# FULL_HIERARCHICAL_SCHEMATIC.net
KiCad netlist of a schematic drawn in Altium Designer
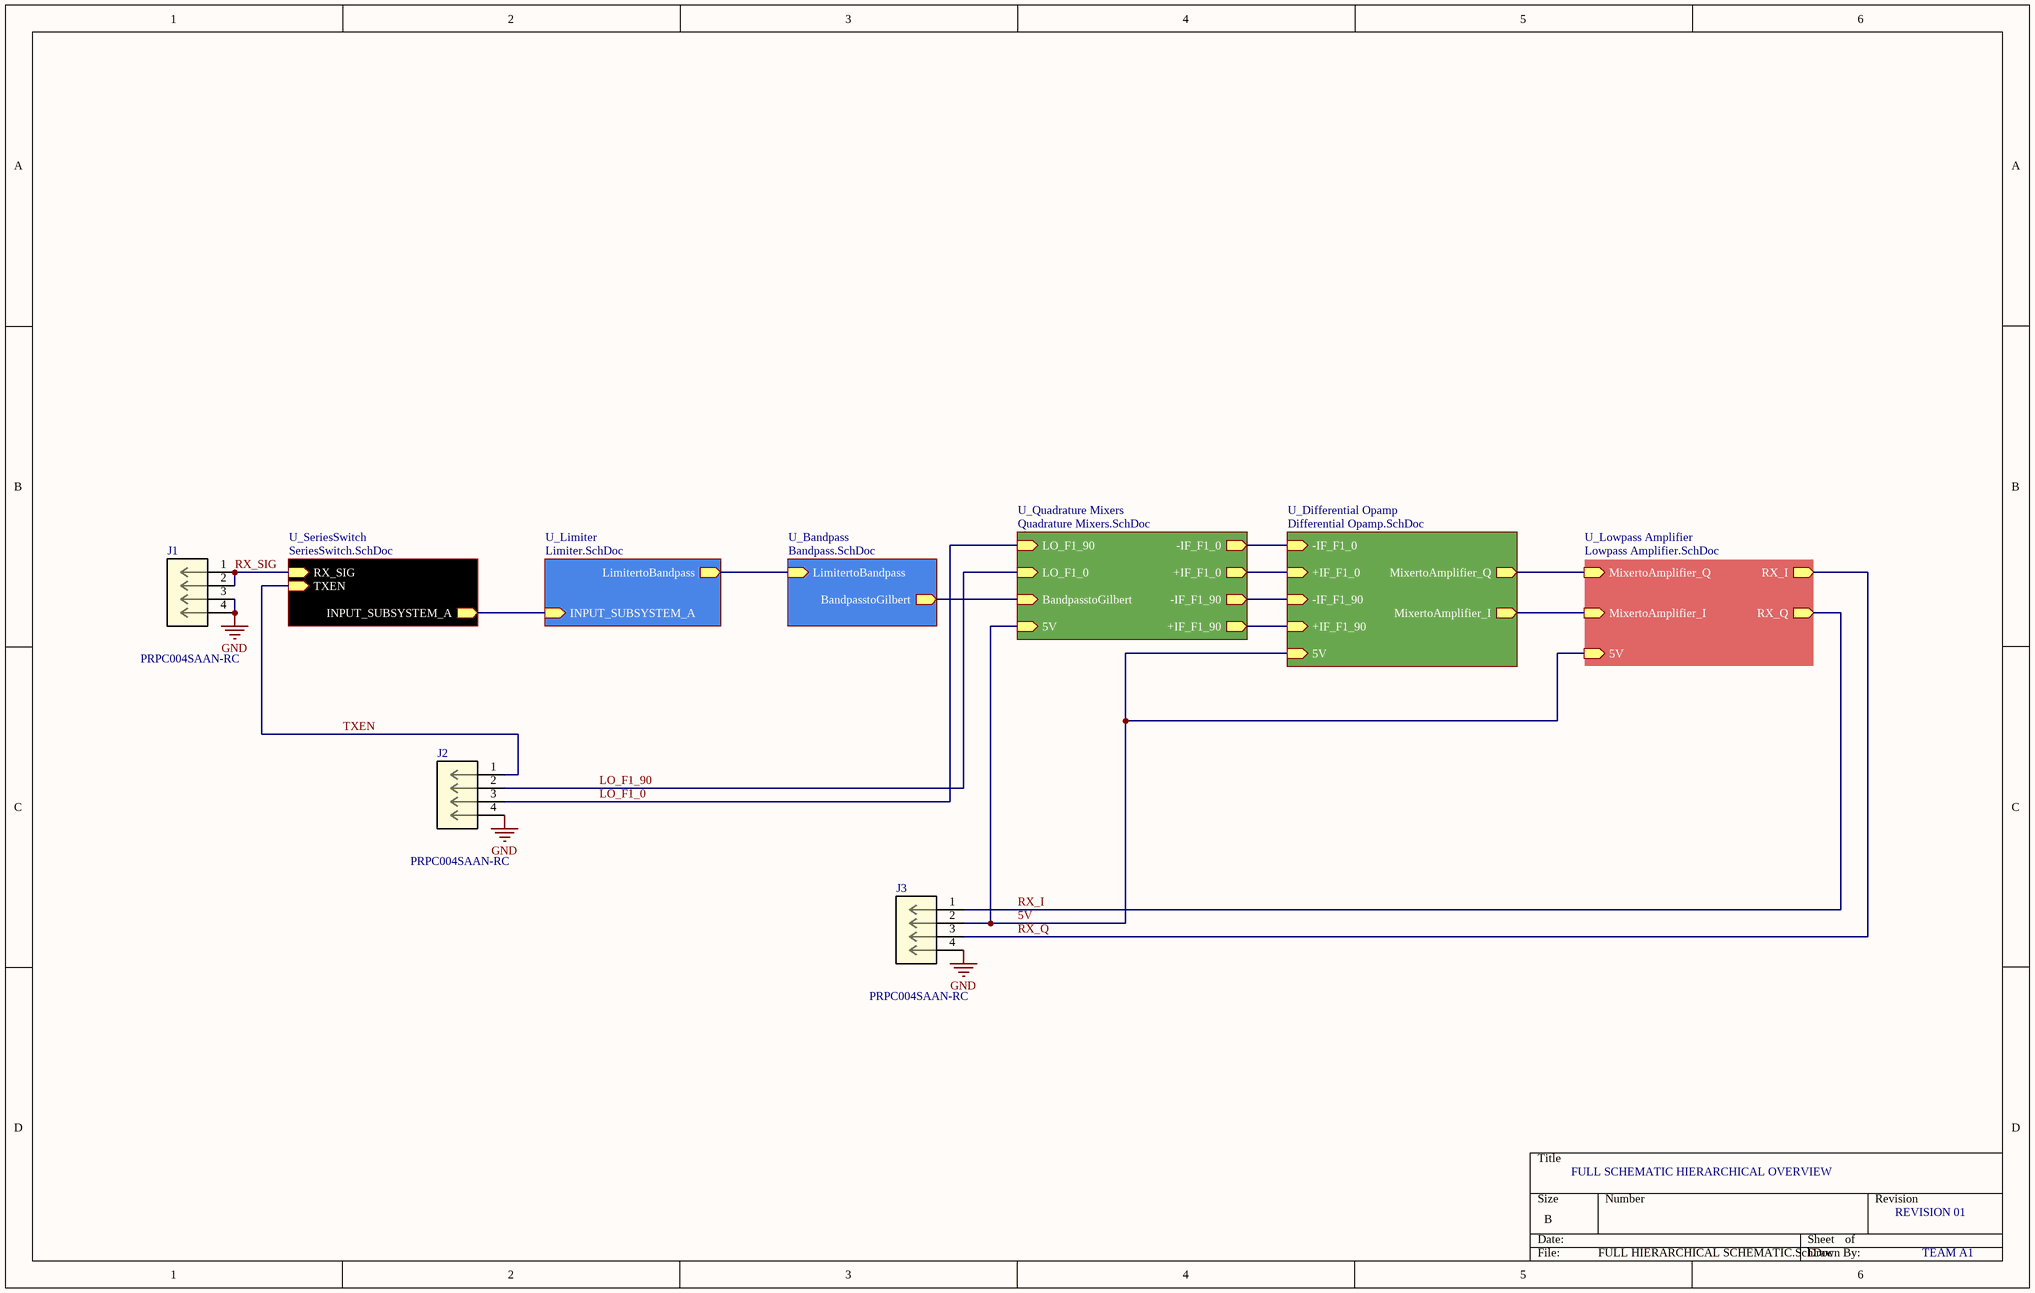
[diagram p0: FULL HIERARCHICAL SCHEMATIC.SchDoc]

(export (version "E")
  (design (tool "Eeschema 10.0.6"))
  (components
    (comp (ref "J1")
      (value "PRPC004SAAN-RC")
      (footprint "CONN4_PRPC004_SUL")
      (description "No Description Available")
      (libsource (lib "PRPC004SAAN-RC") (part "PRPC004SAAN-RC"))
    )
    (comp (ref "J2")
      (value "PRPC004SAAN-RC")
      (footprint "CONN4_PRPC004_SUL")
      (description "No Description Available")
      (libsource (lib "PRPC004SAAN-RC") (part "PRPC004SAAN-RC"))
    )
    (comp (ref "J3")
      (value "PRPC004SAAN-RC")
      (footprint "CONN4_PRPC004_SUL")
      (description "No Description Available")
      (libsource (lib "PRPC004SAAN-RC") (part "PRPC004SAAN-RC"))
    )
  )
  (nets
    (net (code "5") (name "/5V") (class "Default")
      (node (ref "J3") (pin "2") (pinfunction "2_2") (pintype "passive"))
    )
    (net (code "8") (name "/LO_F1_0") (class "Default")
      (node (ref "J2") (pin "3") (pinfunction "3_3") (pintype "passive"))
    )
    (net (code "9") (name "/LO_F1_90") (class "Default")
      (node (ref "J2") (pin "2") (pinfunction "2_2") (pintype "passive"))
    )
    (net (code "13") (name "/RX_I") (class "Default")
      (node (ref "J3") (pin "1") (pinfunction "1_1") (pintype "passive"))
    )
    (net (code "14") (name "/RX_Q") (class "Default")
      (node (ref "J3") (pin "3") (pinfunction "3_3") (pintype "passive"))
    )
    (net (code "15") (name "/RX_SIG") (class "Default")
      (node (ref "J1") (pin "1") (pinfunction "1_1") (pintype "passive"))
      (node (ref "J1") (pin "2") (pinfunction "2_2") (pintype "passive"))
    )
    (net (code "16") (name "/TXEN") (class "Default")
      (node (ref "J2") (pin "1") (pinfunction "1_1") (pintype "passive"))
    )
    (net (code "17") (name "GND") (class "Default")
      (node (ref "J1") (pin "3") (pinfunction "3_3") (pintype "passive"))
      (node (ref "J1") (pin "4") (pinfunction "4_4") (pintype "passive"))
      (node (ref "J2") (pin "4") (pinfunction "4_4") (pintype "passive"))
      (node (ref "J3") (pin "4") (pinfunction "4_4") (pintype "passive"))
    )
  )
)
